# DCDCDC.net
KiCad netlist of a schematic drawn in Altium Designer
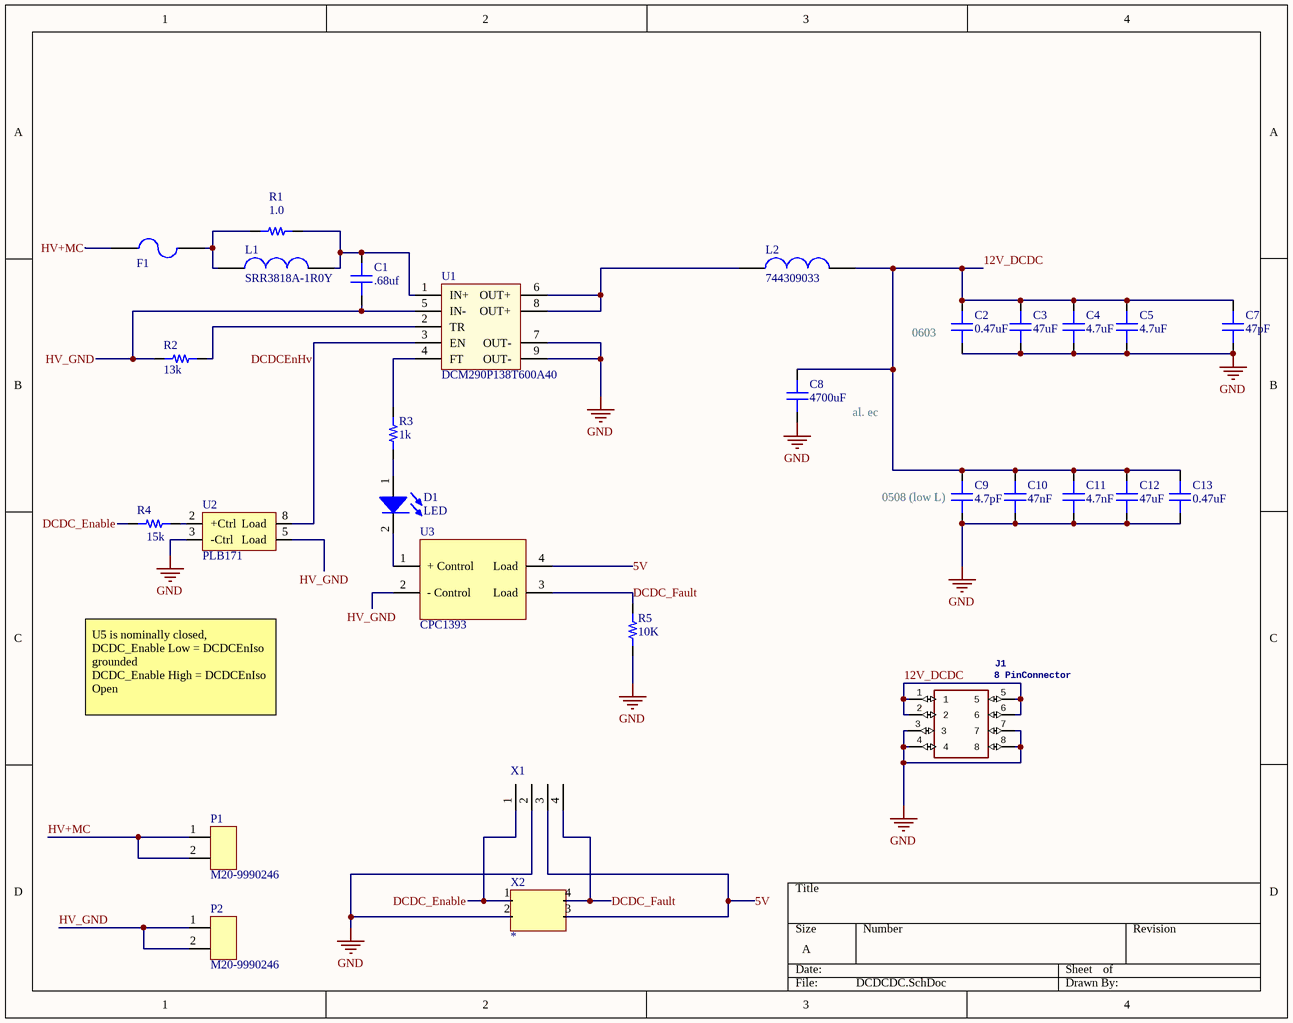
[diagram p0: DCDCDC.SchDoc]

(export (version "E")
  (design (tool "Eeschema 10.0.6"))
  (components
    (comp (ref "C1")
      (value ".68uf")
      (footprint "ECW-FD2W684K-TH-CAP")
      (fields
        (field (name "TOLERANCE") "10%")
        (field (name "MFRPARTNO") "ECW-FD2W684K")
        (field (name "Comment") "HV Cap")
        (field (name "CREATED_BY") "Angel Delgado")
      )
      (libsource (lib "Altium-Lib") (part "Capacitor"))
    )
    (comp (ref "C2")
      (value "capacitor")
      (footprint "0603")
      (description "Generic 0603 capacitor")
      (fields (field (name "CAPACITANCE") "0.47uF") (field (name "VOLTAGE") "50"))
      (libsource (lib "altlib") (part "capacitor"))
    )
    (comp (ref "C3")
      (value "capacitor")
      (footprint "0603")
      (description "Generic 0603 capacitor")
      (fields (field (name "CAPACITANCE") "47uF") (field (name "VOLTAGE") "50"))
      (libsource (lib "altlib") (part "capacitor"))
    )
    (comp (ref "C4")
      (value "capacitor")
      (footprint "0603")
      (description "Generic 0603 capacitor")
      (fields (field (name "CAPACITANCE") "4.7uF") (field (name "VOLTAGE") "50"))
      (libsource (lib "altlib") (part "capacitor"))
    )
    (comp (ref "C5")
      (value "capacitor")
      (footprint "0603")
      (description "Generic 0603 capacitor")
      (fields (field (name "CAPACITANCE") "4.7uF") (field (name "VOLTAGE") "50"))
      (libsource (lib "altlib") (part "capacitor"))
    )
    (comp (ref "C7")
      (value "capacitor")
      (footprint "0603")
      (description "Generic 0603 capacitor")
      (fields (field (name "CAPACITANCE") "47pF") (field (name "VOLTAGE") "50"))
      (libsource (lib "altlib") (part "capacitor"))
    )
    (comp (ref "C8")
      (value "capacitor")
      (footprint "CAP AL TH D16 L7.5 H16.5")
      (description "Generic D16 L7.5 H16.5 capacitor")
      (fields
        (field (name "CAPACITANCE") "4700uF")
        (field (name "VOLTAGE") "0")
        (field (name "CREATEDBY") "Eric Tse")
        (field (name "UPDATEDBY") "Eric Tse")
      )
      (libsource (lib "altlib") (part "capacitor"))
    )
    (comp (ref "C9")
      (value "capacitor")
      (footprint "0508")
      (description "generic 0508 capacitor")
      (fields
        (field (name "CAPACITANCE") "4.7pF")
        (field (name "VOLTAGE") "0")
        (field (name "CREATEDBY") "Eric Tse")
        (field (name "UPDATEDBY") "Eric Tse")
      )
      (libsource (lib "altlib") (part "capacitor"))
    )
    (comp (ref "C10")
      (value "capacitor")
      (footprint "0508")
      (description "generic 0508 capacitor")
      (fields
        (field (name "CAPACITANCE") "47nF")
        (field (name "VOLTAGE") "0")
        (field (name "CREATEDBY") "Eric Tse")
        (field (name "UPDATEDBY") "Eric Tse")
      )
      (libsource (lib "altlib") (part "capacitor"))
    )
    (comp (ref "C11")
      (value "capacitor")
      (footprint "0508")
      (description "generic 0508 capacitor")
      (fields
        (field (name "CAPACITANCE") "4.7nF")
        (field (name "VOLTAGE") "0")
        (field (name "CREATEDBY") "Eric Tse")
        (field (name "UPDATEDBY") "Eric Tse")
      )
      (libsource (lib "altlib") (part "capacitor"))
    )
    (comp (ref "C12")
      (value "capacitor")
      (footprint "0508")
      (description "generic 0508 capacitor")
      (fields
        (field (name "CAPACITANCE") "47uF")
        (field (name "VOLTAGE") "0")
        (field (name "CREATEDBY") "Eric Tse")
        (field (name "UPDATEDBY") "Eric Tse")
      )
      (libsource (lib "altlib") (part "capacitor"))
    )
    (comp (ref "C13")
      (value "capacitor")
      (footprint "0508")
      (description "generic 0508 capacitor")
      (fields
        (field (name "CAPACITANCE") "0.47uF")
        (field (name "VOLTAGE") "0")
        (field (name "CREATEDBY") "Eric Tse")
        (field (name "UPDATEDBY") "Eric Tse")
      )
      (libsource (lib "altlib") (part "capacitor"))
    )
    (comp (ref "D1") (value "LED") (footprint "0805_LED") (libsource (lib "Altium-Lib") (part "LED")))
    (comp (ref "F1") (value "Fuse") (footprint "0885004.DR") (libsource (lib "altlib") (part "Fuse")))
    (comp (ref "J1")
      (value "8 PinConnector")
      (footprint "39-30-0080")
      (description "Connector Header Through Hole, Right Angle 8")
      (fields
        (field (name "RS_PART_NUMBER") "6795852P")
        (field (name "MANUFACTURER_PART_NUMBER") "39-30-0080")
      )
      (libsource (lib "altlib") (part "39-30-0080"))
    )
    (comp (ref "L1")
      (value "SRR3818A-1R0Y")
      (footprint "SRR3818A-1R0Y")
      (description "1uH fixed inductor")
      (fields (field (name "CREATED_BY") "Graydon"))
      (libsource (lib "Altium-Lib") (part "SRR3818A-1R0Y"))
    )
    (comp (ref "L2")
      (value "744309033")
      (footprint "744309033")
      (description "330nH wirewound inductor")
      (fields (field (name "CREATED_BY") "Graydon"))
      (libsource (lib "Altium-Lib") (part "744309033"))
    )
    (comp (ref "P1")
      (value "M20-9990246")
      (footprint "M20-9990246")
      (description "2 Pin VCC Power Header, Male")
      (fields (field (name "CREATED_BY") "Austin") (field (name "UPDATED_BY") "Null"))
      (libsource (lib "Altium-Lib") (part "M20-9990246"))
    )
    (comp (ref "P2")
      (value "M20-9990246")
      (footprint "M20-9990246")
      (description "2 Pin VCC Power Header, Male")
      (fields (field (name "CREATED_BY") "Austin") (field (name "UPDATED_BY") "Null"))
      (libsource (lib "Altium-Lib") (part "M20-9990246"))
    )
    (comp (ref "R1")
      (value "1.0")
      (footprint "RES 0603/1608")
      (fields
        (field (name "TOLERANCE") "1%")
        (field (name "POWER") "1/10W")
        (field (name "Comment") "Resistor 1.0 0603 1/10W 1%")
        (field (name "CREATED_BY") "Nick Mah")
      )
      (libsource (lib "Altium-Lib") (part "Resistor"))
    )
    (comp (ref "R2")
      (value "13k")
      (footprint "RES 0603/1608")
      (fields
        (field (name "TOLERANCE") "1%")
        (field (name "POWER") "1/10W")
        (field (name "Comment") "Resistor 13k 0603 1/10W 1%")
        (field (name "CREATED_BY") "Nick Mah")
      )
      (libsource (lib "Altium-Lib") (part "Resistor"))
    )
    (comp (ref "R3")
      (value "1k")
      (footprint "RES 0603/1608")
      (fields
        (field (name "TOLERANCE") "1%")
        (field (name "POWER") "1/10W")
        (field (name "Comment") "Resistor 330 0603 1/10W 1%")
        (field (name "CREATED_BY") "Nick Mah")
      )
      (libsource (lib "Altium-Lib") (part "Resistor"))
    )
    (comp (ref "R4")
      (value "15k")
      (footprint "RES 0603/1608")
      (fields
        (field (name "TOLERANCE") "1%")
        (field (name "POWER") "1/10W")
        (field (name "Comment") "Resistor 3.0k 0603 1/10W 1%")
        (field (name "CREATED_BY") "Nick Mah")
      )
      (libsource (lib "Altium-Lib") (part "Resistor"))
    )
    (comp (ref "R5")
      (value "10K")
      (footprint "RES 0603/1608")
      (fields (field (name "RESISTANCE") "10K"))
      (libsource (lib "altlib") (part "Resistor"))
    )
    (comp (ref "U1")
      (value "DCM290P138T600A40")
      (footprint "DCM290P138T600A40")
      (description "Vicor DC/DC converter")
      (fields (field (name "CREATED_BY") "Graydon"))
      (libsource (lib "Altium-Lib") (part "DCM290P138T600A40"))
    )
    (comp (ref "U2") (value "PLB171") (footprint "PLB171P") (libsource (lib "altlib") (part "PLB171")))
    (comp (ref "U3")
      (value "CPC1393")
      (footprint "CPC1393GR")
      (description "Solid State Relay SPST-NO (1 Form A) 4-SMD (0.300\", 7.62mm)")
      (fields
        (field (name "MFRPARTNO") "CPC1393GRTR")
        (field (name "CREATED_BY") "Lynette")
        (field (name "UPDATED_BY") "Null")
      )
      (libsource (lib "Altium-Lib") (part "CPC1393"))
    )
    (comp (ref "X1")
      (value "4 pin header")
      (footprint "4pinheader")
      (libsource (lib "altlib") (part "4pinheader"))
    )
    (comp (ref "X2")
      (value "*")
      (footprint "Molex_43650_0402")
      (description "Molex 43650_0402")
      (libsource (lib "altlib") (part "CONN 4POS"))
    )
  )
  (nets
    (net (code "1") (name "/5V") (class "Default")
      (node (ref "U3") (pin "4") (pinfunction "Load_4") (pintype "passive"))
      (node (ref "X1") (pin "3") (pintype "passive"))
      (node (ref "X2") (pin "3") (pintype "input"))
    )
    (net (code "2") (name "/12V_DCDC") (class "Default")
      (node (ref "C10") (pin "2") (pinfunction "2_2") (pintype "passive"))
      (node (ref "C11") (pin "2") (pinfunction "2_2") (pintype "passive"))
      (node (ref "C12") (pin "2") (pinfunction "2_2") (pintype "passive"))
      (node (ref "C13") (pin "2") (pinfunction "2_2") (pintype "passive"))
      (node (ref "C2") (pin "2") (pinfunction "2_2") (pintype "passive"))
      (node (ref "C3") (pin "2") (pinfunction "2_2") (pintype "passive"))
      (node (ref "C4") (pin "2") (pinfunction "2_2") (pintype "passive"))
      (node (ref "C5") (pin "2") (pinfunction "2_2") (pintype "passive"))
      (node (ref "C7") (pin "2") (pinfunction "2_2") (pintype "passive"))
      (node (ref "C8") (pin "2") (pinfunction "2_2") (pintype "passive"))
      (node (ref "C9") (pin "2") (pinfunction "2_2") (pintype "passive"))
      (node (ref "J1") (pin "1") (pinfunction "1_1") (pintype "bidirectional"))
      (node (ref "J1") (pin "2") (pinfunction "2_2") (pintype "bidirectional"))
      (node (ref "J1") (pin "5") (pinfunction "5_5") (pintype "bidirectional"))
      (node (ref "J1") (pin "6") (pinfunction "6_6") (pintype "bidirectional"))
      (node (ref "L2") (pin "2") (pinfunction "2_2") (pintype "power_in"))
    )
    (net (code "3") (name "/DCDCEnHv") (class "Default")
      (node (ref "U1") (pin "3") (pinfunction "EN_3") (pintype "power_in"))
      (node (ref "U2") (pin "8") (pinfunction "Load_8") (pintype "passive"))
    )
    (net (code "4") (name "/DCDC_Enable") (class "Default")
      (node (ref "R4") (pin "1") (pinfunction "1_1") (pintype "passive"))
      (node (ref "X1") (pin "1") (pintype "passive"))
      (node (ref "X2") (pin "1") (pintype "input"))
    )
    (net (code "5") (name "/DCDC_Fault") (class "Default")
      (node (ref "R5") (pin "2") (pinfunction "2_2") (pintype "passive"))
      (node (ref "U3") (pin "3") (pinfunction "Load_3") (pintype "passive"))
      (node (ref "X1") (pin "4") (pintype "passive"))
      (node (ref "X2") (pin "4") (pintype "input"))
    )
    (net (code "6") (name "/HV+MC") (class "Default")
      (node (ref "F1") (pin "2") (pinfunction "2_2") (pintype "passive"))
      (node (ref "P1") (pin "1") (pintype "passive"))
      (node (ref "P1") (pin "2") (pintype "passive"))
    )
    (net (code "7") (name "/HV_GND") (class "Default")
      (node (ref "C1") (pin "2") (pinfunction "2_2") (pintype "passive"))
      (node (ref "P2") (pin "1") (pintype "passive"))
      (node (ref "P2") (pin "2") (pintype "passive"))
      (node (ref "R2") (pin "2") (pinfunction "2_2") (pintype "passive"))
      (node (ref "U1") (pin "5") (pinfunction "IN-_5") (pintype "power_in"))
      (node (ref "U2") (pin "5") (pinfunction "Load_5") (pintype "passive"))
      (node (ref "U3") (pin "2") (pinfunction "-_Control_2") (pintype "passive"))
    )
    (net (code "8") (name "GND") (class "Default")
      (node (ref "C10") (pin "1") (pinfunction "1_1") (pintype "passive"))
      (node (ref "C11") (pin "1") (pinfunction "1_1") (pintype "passive"))
      (node (ref "C12") (pin "1") (pinfunction "1_1") (pintype "passive"))
      (node (ref "C13") (pin "1") (pinfunction "1_1") (pintype "passive"))
      (node (ref "C2") (pin "1") (pinfunction "1_1") (pintype "passive"))
      (node (ref "C3") (pin "1") (pinfunction "1_1") (pintype "passive"))
      (node (ref "C4") (pin "1") (pinfunction "1_1") (pintype "passive"))
      (node (ref "C5") (pin "1") (pinfunction "1_1") (pintype "passive"))
      (node (ref "C7") (pin "1") (pinfunction "1_1") (pintype "passive"))
      (node (ref "C8") (pin "1") (pinfunction "1_1") (pintype "passive"))
      (node (ref "C9") (pin "1") (pinfunction "1_1") (pintype "passive"))
      (node (ref "J1") (pin "3") (pinfunction "3_3") (pintype "bidirectional"))
      (node (ref "J1") (pin "4") (pinfunction "4_4") (pintype "bidirectional"))
      (node (ref "J1") (pin "7") (pinfunction "7_7") (pintype "bidirectional"))
      (node (ref "J1") (pin "8") (pinfunction "8_8") (pintype "bidirectional"))
      (node (ref "R5") (pin "1") (pinfunction "1_1") (pintype "passive"))
      (node (ref "U1") (pin "7") (pinfunction "OUT-_7") (pintype "power_in"))
      (node (ref "U1") (pin "9") (pinfunction "OUT-_9") (pintype "power_in"))
      (node (ref "U2") (pin "3") (pinfunction "-Ctrl_3") (pintype "passive"))
      (node (ref "X1") (pin "2") (pintype "passive"))
      (node (ref "X2") (pin "2") (pintype "input"))
    )
    (net (code "9") (name "Net-(D1-A)") (class "Default")
      (node (ref "D1") (pin "1") (pinfunction "A_1") (pintype "passive"))
      (node (ref "R3") (pin "1") (pinfunction "1_1") (pintype "passive"))
    )
    (net (code "10") (name "Net-(D1-K)") (class "Default")
      (node (ref "D1") (pin "2") (pinfunction "K_2") (pintype "passive"))
      (node (ref "U3") (pin "1") (pinfunction "+_Control_1") (pintype "passive"))
    )
    (net (code "11") (name "Net-(F1-Pad1)") (class "Default")
      (node (ref "F1") (pin "1") (pinfunction "1_1") (pintype "passive"))
      (node (ref "L1") (pin "1") (pintype "power_in"))
      (node (ref "R1") (pin "1") (pinfunction "1_1") (pintype "passive"))
    )
    (net (code "12") (name "Net-(L2-Pad1)") (class "Default")
      (node (ref "L2") (pin "1") (pintype "power_in"))
      (node (ref "U1") (pin "6") (pinfunction "OUT+_6") (pintype "power_in"))
      (node (ref "U1") (pin "8") (pinfunction "OUT+_8") (pintype "power_in"))
    )
    (net (code "13") (name "Net-(U1-FT)") (class "Default")
      (node (ref "R3") (pin "2") (pinfunction "2_2") (pintype "passive"))
      (node (ref "U1") (pin "4") (pinfunction "FT_4") (pintype "power_in"))
    )
    (net (code "14") (name "Net-(U1-IN+)") (class "Default")
      (node (ref "C1") (pin "1") (pinfunction "1_1") (pintype "passive"))
      (node (ref "L1") (pin "2") (pinfunction "2_2") (pintype "power_in"))
      (node (ref "R1") (pin "2") (pinfunction "2_2") (pintype "passive"))
      (node (ref "U1") (pin "1") (pinfunction "IN+_1") (pintype "power_in"))
    )
    (net (code "15") (name "Net-(U1-TR)") (class "Default")
      (node (ref "R2") (pin "1") (pinfunction "1_1") (pintype "passive"))
      (node (ref "U1") (pin "2") (pinfunction "TR_2") (pintype "power_in"))
    )
    (net (code "16") (name "Net-(U2-+Ctrl)") (class "Default")
      (node (ref "R4") (pin "2") (pinfunction "2_2") (pintype "passive"))
      (node (ref "U2") (pin "2") (pinfunction "+Ctrl_2") (pintype "passive"))
    )
  )
)
